# M236X.net
KiCad netlist of a schematic drawn in EAGLE
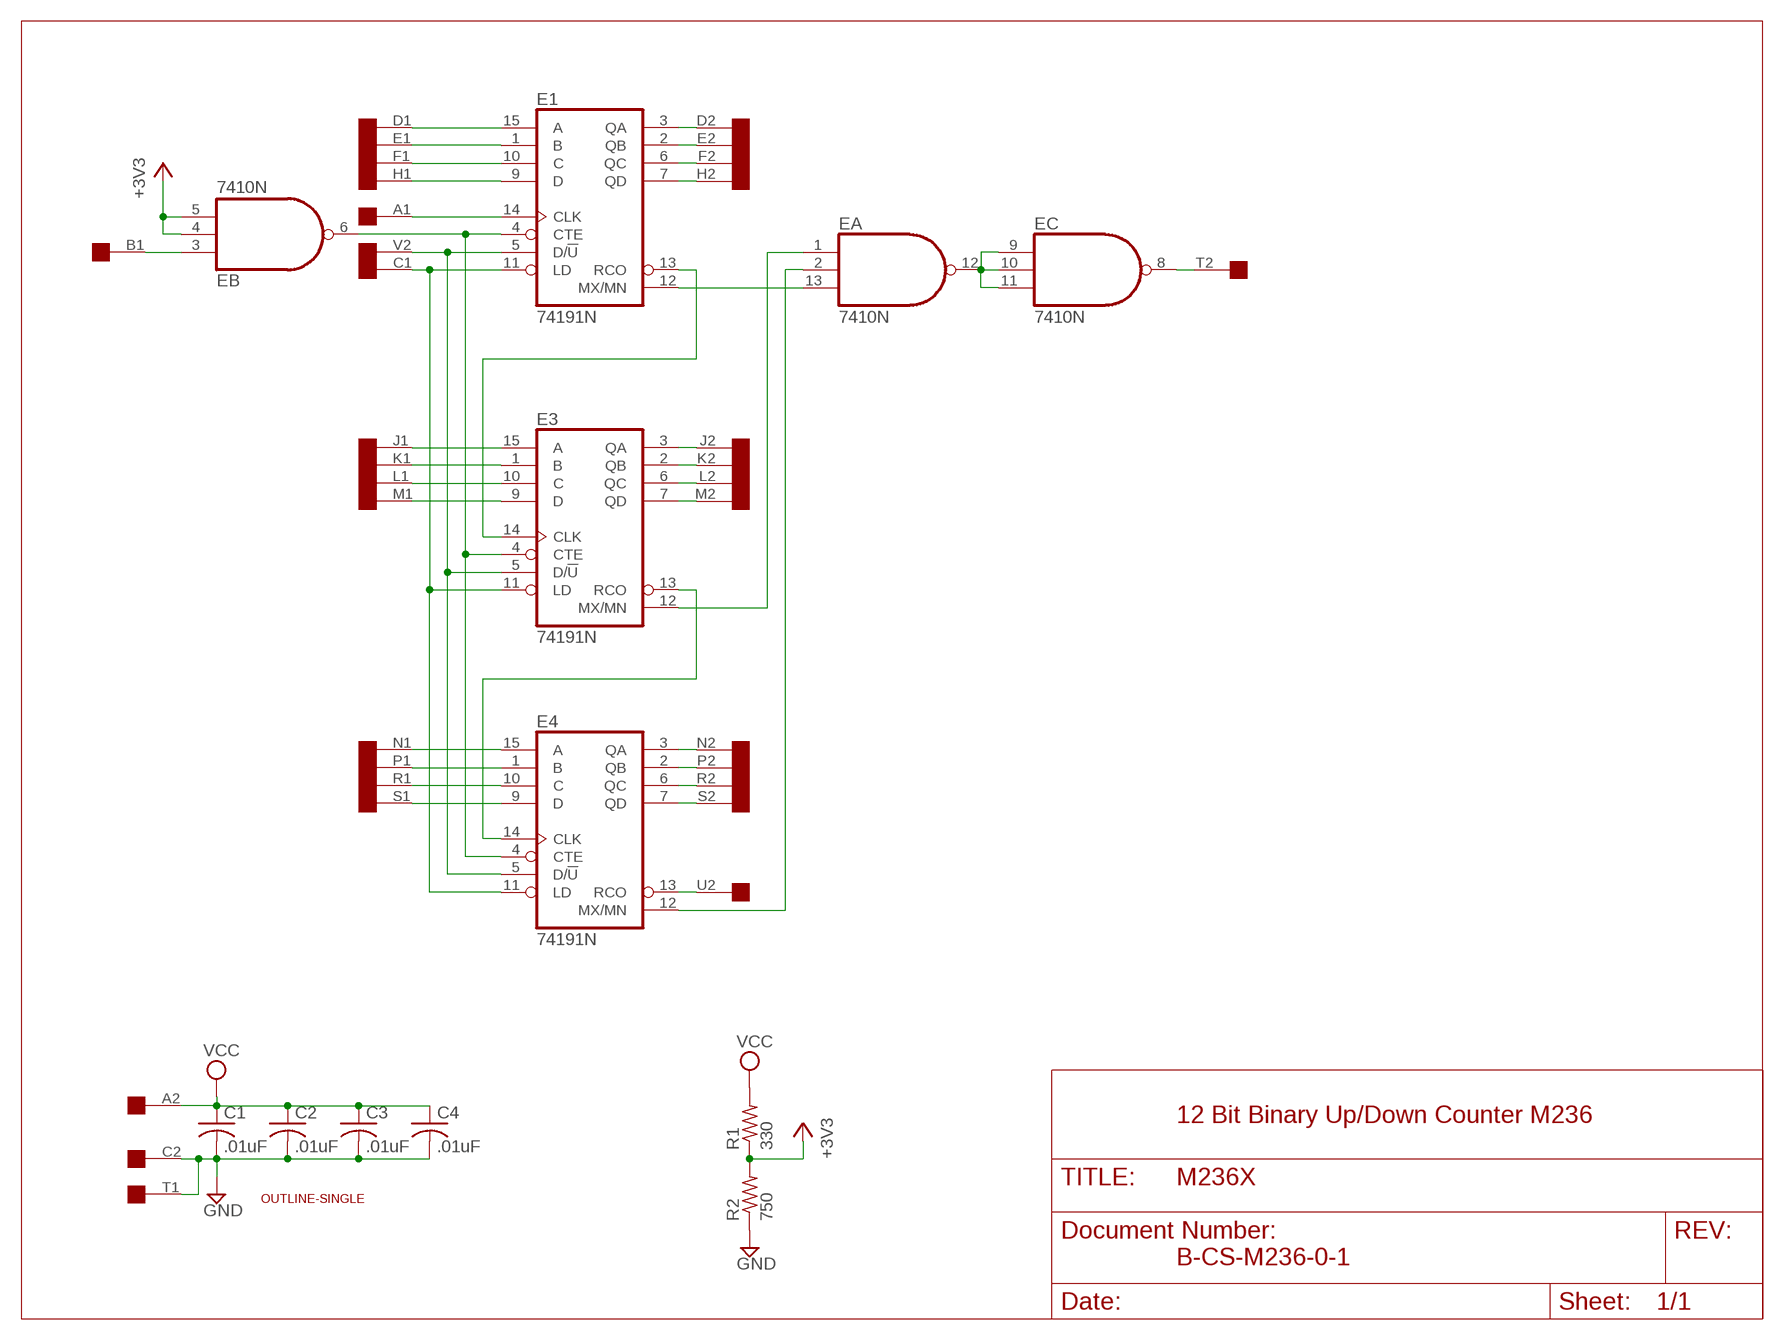
[diagram p0: schematic, sheet 1]

(export (version "E")
  (design (tool "Eeschema 10.0.6"))
  (components
    (comp (ref "C1")
      (value ".01uF")
      (footprint "eagle-import:C050-025X075")
      (libsource (lib "eagle-import") (part "C-US050-025X075"))
    )
    (comp (ref "C2")
      (value ".01uF")
      (footprint "eagle-import:C050-025X075")
      (libsource (lib "eagle-import") (part "C-US050-025X075"))
    )
    (comp (ref "C3")
      (value ".01uF")
      (footprint "eagle-import:C050-025X075")
      (libsource (lib "eagle-import") (part "C-US050-025X075"))
    )
    (comp (ref "C4")
      (value ".01uF")
      (footprint "eagle-import:C050-025X075")
      (libsource (lib "eagle-import") (part "C-US050-025X075"))
    )
    (comp (ref "E")
      (value "7410N")
      (footprint "eagle-import:DIL14")
      (libsource (lib "eagle-import") (part "7410N"))
    )
    (comp (ref "E1")
      (value "74191N")
      (footprint "eagle-import:DIL16")
      (libsource (lib "eagle-import") (part "74191N"))
    )
    (comp (ref "E3")
      (value "74191N")
      (footprint "eagle-import:DIL16")
      (libsource (lib "eagle-import") (part "74191N"))
    )
    (comp (ref "E4")
      (value "74191N")
      (footprint "eagle-import:DIL16")
      (libsource (lib "eagle-import") (part "74191N"))
    )
    (comp (ref "R1")
      (value "330")
      (footprint "eagle-import:0207_10")
      (libsource (lib "eagle-import") (part "R-US_0207/10"))
    )
    (comp (ref "R2")
      (value "750")
      (footprint "eagle-import:0207_10")
      (libsource (lib "eagle-import") (part "R-US_0207/10"))
    )
    (comp (ref "U$1")
      (value "OUTLINE-SINGLE")
      (footprint "eagle-import:SINGLE")
      (libsource (lib "eagle-import") (part "OUTLINE-SINGLE"))
    )
    (comp (ref "U$2")
      (value "SINGLE")
      (footprint "eagle-import:EDGE-CON2")
      (libsource (lib "eagle-import") (part "SINGLE"))
    )
  )
  (nets
    (net (code "1") (name "+3V3") (class "Default")
      (node (ref "E") (pin "4") (pinfunction "I1_4") (pintype "input"))
      (node (ref "E") (pin "5") (pinfunction "I2_5") (pintype "input"))
      (node (ref "R1") (pin "1") (pinfunction "1_1") (pintype "passive"))
      (node (ref "R2") (pin "2") (pinfunction "2_2") (pintype "passive"))
    )
    (net (code "2") (name "GND") (class "Default")
      (node (ref "C1") (pin "2") (pinfunction "2_2") (pintype "passive"))
      (node (ref "C2") (pin "2") (pinfunction "2_2") (pintype "passive"))
      (node (ref "C3") (pin "2") (pinfunction "2_2") (pintype "passive"))
      (node (ref "C4") (pin "2") (pinfunction "2_2") (pintype "passive"))
      (node (ref "R2") (pin "1") (pinfunction "1_1") (pintype "passive"))
      (node (ref "U$2") (pin "C2") (pinfunction "1_C2") (pintype "bidirectional"))
      (node (ref "U$2") (pin "T1") (pinfunction "1_T1") (pintype "bidirectional"))
    )
    (net (code "3") (name "Net-(E1A-A)") (class "Default")
      (node (ref "E1") (pin "15") (pinfunction "A_15") (pintype "input"))
      (node (ref "U$2") (pin "D1") (pinfunction "1_D1") (pintype "bidirectional"))
    )
    (net (code "4") (name "Net-(E1A-B)") (class "Default")
      (node (ref "E1") (pin "1") (pinfunction "B_1") (pintype "input"))
      (node (ref "U$2") (pin "E1") (pinfunction "1_E1") (pintype "bidirectional"))
    )
    (net (code "5") (name "Net-(E1A-C)") (class "Default")
      (node (ref "E1") (pin "10") (pinfunction "C_10") (pintype "input"))
      (node (ref "U$2") (pin "F1") (pinfunction "1_F1") (pintype "bidirectional"))
    )
    (net (code "6") (name "Net-(E1A-CLK)") (class "Default")
      (node (ref "E1") (pin "14") (pinfunction "CLK_14") (pintype "input"))
      (node (ref "U$2") (pin "A1") (pinfunction "1_A1") (pintype "bidirectional"))
    )
    (net (code "7") (name "Net-(E1A-CTE)") (class "Default")
      (node (ref "E") (pin "6") (pinfunction "O_6") (pintype "output"))
      (node (ref "E1") (pin "4") (pinfunction "CTE_4") (pintype "input"))
      (node (ref "E3") (pin "4") (pinfunction "CTE_4") (pintype "input"))
      (node (ref "E4") (pin "4") (pinfunction "CTE_4") (pintype "input"))
    )
    (net (code "8") (name "Net-(E1A-D)") (class "Default")
      (node (ref "E1") (pin "9") (pinfunction "D_9") (pintype "input"))
      (node (ref "U$2") (pin "H1") (pinfunction "1_H1") (pintype "bidirectional"))
    )
    (net (code "9") (name "Net-(E1A-D{slash}~{U})") (class "Default")
      (node (ref "E1") (pin "5") (pinfunction "D/~{U}_5") (pintype "input"))
      (node (ref "E3") (pin "5") (pinfunction "D/~{U}_5") (pintype "input"))
      (node (ref "E4") (pin "5") (pinfunction "D/~{U}_5") (pintype "input"))
      (node (ref "U$2") (pin "V2") (pinfunction "1_V2") (pintype "bidirectional"))
    )
    (net (code "10") (name "Net-(E1A-LD)") (class "Default")
      (node (ref "E1") (pin "11") (pinfunction "LD_11") (pintype "input"))
      (node (ref "E3") (pin "11") (pinfunction "LD_11") (pintype "input"))
      (node (ref "E4") (pin "11") (pinfunction "LD_11") (pintype "input"))
      (node (ref "U$2") (pin "C1") (pinfunction "1_C1") (pintype "bidirectional"))
    )
    (net (code "11") (name "Net-(E1A-MX{slash}MN)") (class "Default")
      (node (ref "E") (pin "13") (pinfunction "I2_13") (pintype "input"))
      (node (ref "E1") (pin "12") (pinfunction "MX/MN_12") (pintype "output"))
    )
    (net (code "12") (name "Net-(E1A-QA)") (class "Default")
      (node (ref "E1") (pin "3") (pinfunction "QA_3") (pintype "output"))
      (node (ref "U$2") (pin "D2") (pinfunction "1_D2") (pintype "bidirectional"))
    )
    (net (code "13") (name "Net-(E1A-QB)") (class "Default")
      (node (ref "E1") (pin "2") (pinfunction "QB_2") (pintype "output"))
      (node (ref "U$2") (pin "E2") (pinfunction "1_E2") (pintype "bidirectional"))
    )
    (net (code "14") (name "Net-(E1A-QC)") (class "Default")
      (node (ref "E1") (pin "6") (pinfunction "QC_6") (pintype "output"))
      (node (ref "U$2") (pin "F2") (pinfunction "1_F2") (pintype "bidirectional"))
    )
    (net (code "15") (name "Net-(E1A-QD)") (class "Default")
      (node (ref "E1") (pin "7") (pinfunction "QD_7") (pintype "output"))
      (node (ref "U$2") (pin "H2") (pinfunction "1_H2") (pintype "bidirectional"))
    )
    (net (code "16") (name "Net-(E1A-RCO)") (class "Default")
      (node (ref "E1") (pin "13") (pinfunction "RCO_13") (pintype "output"))
      (node (ref "E3") (pin "14") (pinfunction "CLK_14") (pintype "input"))
    )
    (net (code "17") (name "Net-(E3A-A)") (class "Default")
      (node (ref "E3") (pin "15") (pinfunction "A_15") (pintype "input"))
      (node (ref "U$2") (pin "J1") (pinfunction "1_J1") (pintype "bidirectional"))
    )
    (net (code "18") (name "Net-(E3A-B)") (class "Default")
      (node (ref "E3") (pin "1") (pinfunction "B_1") (pintype "input"))
      (node (ref "U$2") (pin "K1") (pinfunction "1_K1") (pintype "bidirectional"))
    )
    (net (code "19") (name "Net-(E3A-C)") (class "Default")
      (node (ref "E3") (pin "10") (pinfunction "C_10") (pintype "input"))
      (node (ref "U$2") (pin "L1") (pinfunction "1_L1") (pintype "bidirectional"))
    )
    (net (code "20") (name "Net-(E3A-D)") (class "Default")
      (node (ref "E3") (pin "9") (pinfunction "D_9") (pintype "input"))
      (node (ref "U$2") (pin "M1") (pinfunction "1_M1") (pintype "bidirectional"))
    )
    (net (code "21") (name "Net-(E3A-MX{slash}MN)") (class "Default")
      (node (ref "E") (pin "1") (pinfunction "I0_1") (pintype "input"))
      (node (ref "E3") (pin "12") (pinfunction "MX/MN_12") (pintype "output"))
    )
    (net (code "22") (name "Net-(E3A-QA)") (class "Default")
      (node (ref "E3") (pin "3") (pinfunction "QA_3") (pintype "output"))
      (node (ref "U$2") (pin "J2") (pinfunction "1_J2") (pintype "bidirectional"))
    )
    (net (code "23") (name "Net-(E3A-QB)") (class "Default")
      (node (ref "E3") (pin "2") (pinfunction "QB_2") (pintype "output"))
      (node (ref "U$2") (pin "K2") (pinfunction "1_K2") (pintype "bidirectional"))
    )
    (net (code "24") (name "Net-(E3A-QC)") (class "Default")
      (node (ref "E3") (pin "6") (pinfunction "QC_6") (pintype "output"))
      (node (ref "U$2") (pin "L2") (pinfunction "1_L2") (pintype "bidirectional"))
    )
    (net (code "25") (name "Net-(E3A-QD)") (class "Default")
      (node (ref "E3") (pin "7") (pinfunction "QD_7") (pintype "output"))
      (node (ref "U$2") (pin "M2") (pinfunction "1_M2") (pintype "bidirectional"))
    )
    (net (code "26") (name "Net-(E3A-RCO)") (class "Default")
      (node (ref "E3") (pin "13") (pinfunction "RCO_13") (pintype "output"))
      (node (ref "E4") (pin "14") (pinfunction "CLK_14") (pintype "input"))
    )
    (net (code "27") (name "Net-(E4A-A)") (class "Default")
      (node (ref "E4") (pin "15") (pinfunction "A_15") (pintype "input"))
      (node (ref "U$2") (pin "N1") (pinfunction "1_N1") (pintype "bidirectional"))
    )
    (net (code "28") (name "Net-(E4A-B)") (class "Default")
      (node (ref "E4") (pin "1") (pinfunction "B_1") (pintype "input"))
      (node (ref "U$2") (pin "P1") (pinfunction "1_P1") (pintype "bidirectional"))
    )
    (net (code "29") (name "Net-(E4A-C)") (class "Default")
      (node (ref "E4") (pin "10") (pinfunction "C_10") (pintype "input"))
      (node (ref "U$2") (pin "R1") (pinfunction "1_R1") (pintype "bidirectional"))
    )
    (net (code "30") (name "Net-(E4A-D)") (class "Default")
      (node (ref "E4") (pin "9") (pinfunction "D_9") (pintype "input"))
      (node (ref "U$2") (pin "S1") (pinfunction "1_S1") (pintype "bidirectional"))
    )
    (net (code "31") (name "Net-(E4A-MX{slash}MN)") (class "Default")
      (node (ref "E") (pin "2") (pinfunction "I1_2") (pintype "input"))
      (node (ref "E4") (pin "12") (pinfunction "MX/MN_12") (pintype "output"))
    )
    (net (code "32") (name "Net-(E4A-QA)") (class "Default")
      (node (ref "E4") (pin "3") (pinfunction "QA_3") (pintype "output"))
      (node (ref "U$2") (pin "N2") (pinfunction "1_N2") (pintype "bidirectional"))
    )
    (net (code "33") (name "Net-(E4A-QB)") (class "Default")
      (node (ref "E4") (pin "2") (pinfunction "QB_2") (pintype "output"))
      (node (ref "U$2") (pin "P2") (pinfunction "1_P2") (pintype "bidirectional"))
    )
    (net (code "34") (name "Net-(E4A-QC)") (class "Default")
      (node (ref "E4") (pin "6") (pinfunction "QC_6") (pintype "output"))
      (node (ref "U$2") (pin "R2") (pinfunction "1_R2") (pintype "bidirectional"))
    )
    (net (code "35") (name "Net-(E4A-QD)") (class "Default")
      (node (ref "E4") (pin "7") (pinfunction "QD_7") (pintype "output"))
      (node (ref "U$2") (pin "S2") (pinfunction "1_S2") (pintype "bidirectional"))
    )
    (net (code "36") (name "Net-(E4A-RCO)") (class "Default")
      (node (ref "E4") (pin "13") (pinfunction "RCO_13") (pintype "output"))
      (node (ref "U$2") (pin "U2") (pinfunction "1_U2") (pintype "bidirectional"))
    )
    (net (code "37") (name "Net-(EA-O)") (class "Default")
      (node (ref "E") (pin "10") (pinfunction "I1_10") (pintype "input"))
      (node (ref "E") (pin "11") (pinfunction "I2_11") (pintype "input"))
      (node (ref "E") (pin "12") (pinfunction "O_12") (pintype "output"))
      (node (ref "E") (pin "9") (pinfunction "I0_9") (pintype "input"))
    )
    (net (code "38") (name "Net-(EB-I0)") (class "Default")
      (node (ref "E") (pin "3") (pinfunction "I0_3") (pintype "input"))
      (node (ref "U$2") (pin "B1") (pinfunction "1_B1") (pintype "bidirectional"))
    )
    (net (code "39") (name "Net-(EC-O)") (class "Default")
      (node (ref "E") (pin "8") (pinfunction "O_8") (pintype "output"))
      (node (ref "U$2") (pin "T2") (pinfunction "1_T2") (pintype "bidirectional"))
    )
    (net (code "40") (name "VCC") (class "Default")
      (node (ref "C1") (pin "1") (pinfunction "1_1") (pintype "passive"))
      (node (ref "C2") (pin "1") (pinfunction "1_1") (pintype "passive"))
      (node (ref "C3") (pin "1") (pinfunction "1_1") (pintype "passive"))
      (node (ref "C4") (pin "1") (pinfunction "1_1") (pintype "passive"))
      (node (ref "R1") (pin "2") (pinfunction "2_2") (pintype "passive"))
      (node (ref "U$2") (pin "A2") (pinfunction "1_A2") (pintype "bidirectional"))
    )
  )
)
